# OLED_Display_Card.net
KiCad netlist of a schematic drawn in EAGLE
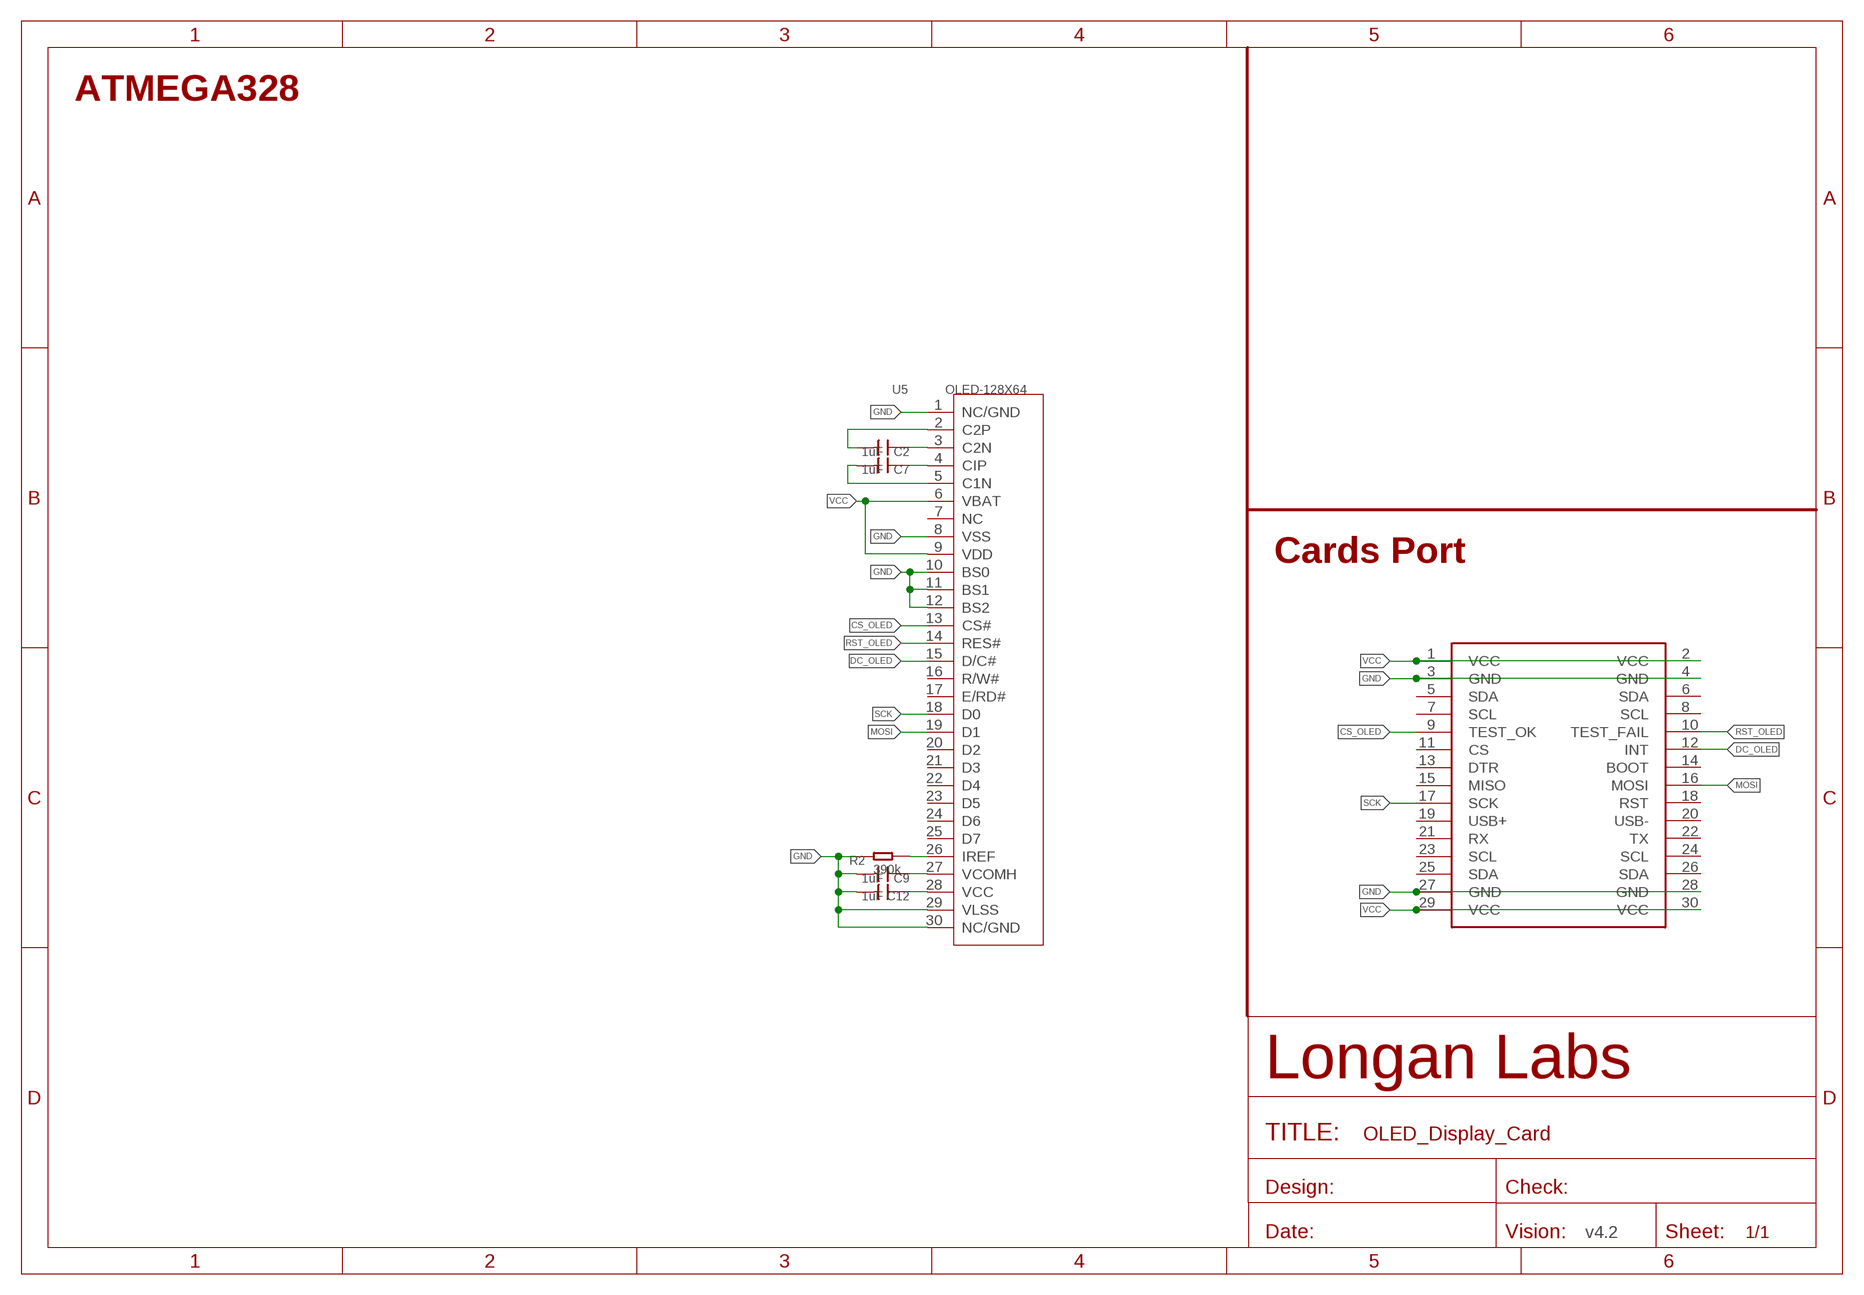
[diagram p0: schematic, sheet 1]

(export (version "E")
  (design (tool "Eeschema 10.0.6"))
  (components
    (comp (ref "C2")
      (value "1uF")
      (footprint "eagle-import:C0603@1")
      (libsource (lib "eagle-import") (part "C-0603"))
    )
    (comp (ref "C7")
      (value "1uF")
      (footprint "eagle-import:C0603@1")
      (libsource (lib "eagle-import") (part "C-0603"))
    )
    (comp (ref "C9")
      (value "1uF")
      (footprint "eagle-import:C0603@1")
      (libsource (lib "eagle-import") (part "C-0603"))
    )
    (comp (ref "C12")
      (value "1uF")
      (footprint "eagle-import:C0603@1")
      (libsource (lib "eagle-import") (part "C-0603"))
    )
    (comp (ref "MOUDLE1")
      (value "MOUDLE-2X15P-2.54")
      (footprint "eagle-import:MOUDLE-2X15P")
      (libsource (lib "eagle-import") (part "MOUDLE-2X15P-2.54"))
    )
    (comp (ref "R2")
      (value "390k")
      (footprint "eagle-import:R0603")
      (libsource (lib "eagle-import") (part "RES-0603"))
    )
    (comp (ref "U5")
      (value "OLED-128X64")
      (footprint "eagle-import:30P-0.7-34.5X12")
      (libsource (lib "eagle-import") (part "OLED-128X64"))
    )
  )
  (nets
    (net (code "1") (name "CS_OLED") (class "Default")
      (node (ref "MOUDLE1") (pin "9") (pinfunction "TEST_OK_9") (pintype "bidirectional"))
      (node (ref "U5") (pin "13") (pinfunction "CS#_13") (pintype "bidirectional"))
    )
    (net (code "2") (name "DC_OLED") (class "Default")
      (node (ref "MOUDLE1") (pin "12") (pinfunction "INT_12") (pintype "bidirectional"))
      (node (ref "U5") (pin "15") (pinfunction "D/C#_15") (pintype "bidirectional"))
    )
    (net (code "3") (name "GND") (class "Default")
      (node (ref "C12") (pin "2") (pinfunction "2_2") (pintype "passive"))
      (node (ref "C9") (pin "2") (pinfunction "2_2") (pintype "passive"))
      (node (ref "MOUDLE1") (pin "27") (pinfunction "GND_27") (pintype "bidirectional"))
      (node (ref "MOUDLE1") (pin "28") (pinfunction "GND_28") (pintype "bidirectional"))
      (node (ref "MOUDLE1") (pin "3") (pinfunction "GND_3") (pintype "bidirectional"))
      (node (ref "MOUDLE1") (pin "4") (pinfunction "GND_4") (pintype "bidirectional"))
      (node (ref "R2") (pin "1") (pinfunction "1_1") (pintype "passive"))
      (node (ref "U5") (pin "1") (pinfunction "NC/GND_1") (pintype "bidirectional"))
      (node (ref "U5") (pin "10") (pinfunction "BS0_10") (pintype "bidirectional"))
      (node (ref "U5") (pin "11") (pinfunction "BS1_11") (pintype "bidirectional"))
      (node (ref "U5") (pin "12") (pinfunction "BS2_12") (pintype "bidirectional"))
      (node (ref "U5") (pin "29") (pinfunction "VLSS_29") (pintype "bidirectional"))
      (node (ref "U5") (pin "30") (pinfunction "NC/GND_30") (pintype "bidirectional"))
      (node (ref "U5") (pin "8") (pinfunction "VSS_8") (pintype "bidirectional"))
    )
    (net (code "4") (name "MOSI") (class "Default")
      (node (ref "MOUDLE1") (pin "16") (pinfunction "MOSI_16") (pintype "bidirectional"))
      (node (ref "U5") (pin "19") (pinfunction "D1_19") (pintype "bidirectional"))
    )
    (net (code "5") (name "Net-(U5-C1N)") (class "Default")
      (node (ref "C7") (pin "2") (pinfunction "2_2") (pintype "passive"))
      (node (ref "U5") (pin "5") (pinfunction "C1N_5") (pintype "bidirectional"))
    )
    (net (code "6") (name "Net-(U5-C2N)") (class "Default")
      (node (ref "C2") (pin "1") (pinfunction "1_1") (pintype "passive"))
      (node (ref "U5") (pin "3") (pinfunction "C2N_3") (pintype "bidirectional"))
    )
    (net (code "7") (name "Net-(U5-C2P)") (class "Default")
      (node (ref "C2") (pin "2") (pinfunction "2_2") (pintype "passive"))
      (node (ref "U5") (pin "2") (pinfunction "C2P_2") (pintype "bidirectional"))
    )
    (net (code "8") (name "Net-(U5-CIP)") (class "Default")
      (node (ref "C7") (pin "1") (pinfunction "1_1") (pintype "passive"))
      (node (ref "U5") (pin "4") (pinfunction "CIP_4") (pintype "bidirectional"))
    )
    (net (code "9") (name "Net-(U5-IREF)") (class "Default")
      (node (ref "R2") (pin "2") (pinfunction "2_2") (pintype "passive"))
      (node (ref "U5") (pin "26") (pinfunction "IREF_26") (pintype "bidirectional"))
    )
    (net (code "10") (name "Net-(U5-VCC)") (class "Default")
      (node (ref "C12") (pin "1") (pinfunction "1_1") (pintype "passive"))
      (node (ref "U5") (pin "28") (pinfunction "VCC_28") (pintype "bidirectional"))
    )
    (net (code "11") (name "Net-(U5-VCOMH)") (class "Default")
      (node (ref "C9") (pin "1") (pinfunction "1_1") (pintype "passive"))
      (node (ref "U5") (pin "27") (pinfunction "VCOMH_27") (pintype "bidirectional"))
    )
    (net (code "12") (name "RST_OLED") (class "Default")
      (node (ref "MOUDLE1") (pin "10") (pinfunction "TEST_FAIL_10") (pintype "bidirectional"))
      (node (ref "U5") (pin "14") (pinfunction "RES#_14") (pintype "bidirectional"))
    )
    (net (code "13") (name "SCK") (class "Default")
      (node (ref "MOUDLE1") (pin "17") (pinfunction "SCK_17") (pintype "bidirectional"))
      (node (ref "U5") (pin "18") (pinfunction "D0_18") (pintype "bidirectional"))
    )
    (net (code "14") (name "VCC") (class "Default")
      (node (ref "MOUDLE1") (pin "1") (pinfunction "VCC_1") (pintype "bidirectional"))
      (node (ref "MOUDLE1") (pin "2") (pinfunction "VCC_2") (pintype "bidirectional"))
      (node (ref "MOUDLE1") (pin "29") (pinfunction "VCC_29") (pintype "bidirectional"))
      (node (ref "MOUDLE1") (pin "30") (pinfunction "VCC_30") (pintype "bidirectional"))
      (node (ref "U5") (pin "6") (pinfunction "VBAT_6") (pintype "bidirectional"))
      (node (ref "U5") (pin "9") (pinfunction "VDD_9") (pintype "bidirectional"))
    )
    (net (code "15") (name "unconnected-(MOUDLE1-BOOT-Pad14)") (class "Default")
      (node (ref "MOUDLE1") (pin "14") (pinfunction "BOOT_14") (pintype "bidirectional"))
    )
    (net (code "16") (name "unconnected-(MOUDLE1-CS-Pad11)") (class "Default")
      (node (ref "MOUDLE1") (pin "11") (pinfunction "CS_11") (pintype "bidirectional"))
    )
    (net (code "17") (name "unconnected-(MOUDLE1-DTR-Pad13)") (class "Default")
      (node (ref "MOUDLE1") (pin "13") (pinfunction "DTR_13") (pintype "bidirectional"))
    )
    (net (code "18") (name "unconnected-(MOUDLE1-MISO-Pad15)") (class "Default")
      (node (ref "MOUDLE1") (pin "15") (pinfunction "MISO_15") (pintype "bidirectional"))
    )
    (net (code "19") (name "unconnected-(MOUDLE1-RST-Pad18)") (class "Default")
      (node (ref "MOUDLE1") (pin "18") (pinfunction "RST_18") (pintype "bidirectional"))
    )
    (net (code "20") (name "unconnected-(MOUDLE1-RX-Pad21)") (class "Default")
      (node (ref "MOUDLE1") (pin "21") (pinfunction "RX_21") (pintype "bidirectional"))
    )
    (net (code "21") (name "unconnected-(MOUDLE1-SCL-Pad7)") (class "Default")
      (node (ref "MOUDLE1") (pin "7") (pinfunction "SCL_7") (pintype "bidirectional"))
    )
    (net (code "22") (name "unconnected-(MOUDLE1-SCL-Pad8)") (class "Default")
      (node (ref "MOUDLE1") (pin "8") (pinfunction "SCL_8") (pintype "bidirectional"))
    )
    (net (code "23") (name "unconnected-(MOUDLE1-SCL-Pad23)") (class "Default")
      (node (ref "MOUDLE1") (pin "23") (pinfunction "SCL_23") (pintype "bidirectional"))
    )
    (net (code "24") (name "unconnected-(MOUDLE1-SCL-Pad24)") (class "Default")
      (node (ref "MOUDLE1") (pin "24") (pinfunction "SCL_24") (pintype "bidirectional"))
    )
    (net (code "25") (name "unconnected-(MOUDLE1-SDA-Pad5)") (class "Default")
      (node (ref "MOUDLE1") (pin "5") (pinfunction "SDA_5") (pintype "bidirectional"))
    )
    (net (code "26") (name "unconnected-(MOUDLE1-SDA-Pad6)") (class "Default")
      (node (ref "MOUDLE1") (pin "6") (pinfunction "SDA_6") (pintype "bidirectional"))
    )
    (net (code "27") (name "unconnected-(MOUDLE1-SDA-Pad25)") (class "Default")
      (node (ref "MOUDLE1") (pin "25") (pinfunction "SDA_25") (pintype "bidirectional"))
    )
    (net (code "28") (name "unconnected-(MOUDLE1-SDA-Pad26)") (class "Default")
      (node (ref "MOUDLE1") (pin "26") (pinfunction "SDA_26") (pintype "bidirectional"))
    )
    (net (code "29") (name "unconnected-(MOUDLE1-TX-Pad22)") (class "Default")
      (node (ref "MOUDLE1") (pin "22") (pinfunction "TX_22") (pintype "bidirectional"))
    )
    (net (code "30") (name "unconnected-(MOUDLE1-USB+-Pad19)") (class "Default")
      (node (ref "MOUDLE1") (pin "19") (pinfunction "USB+_19") (pintype "bidirectional"))
    )
    (net (code "31") (name "unconnected-(MOUDLE1-USB--Pad20)") (class "Default")
      (node (ref "MOUDLE1") (pin "20") (pinfunction "USB-_20") (pintype "bidirectional"))
    )
    (net (code "32") (name "unconnected-(U5-D2-Pad20)") (class "Default")
      (node (ref "U5") (pin "20") (pinfunction "D2_20") (pintype "bidirectional"))
    )
    (net (code "33") (name "unconnected-(U5-D3-Pad21)") (class "Default")
      (node (ref "U5") (pin "21") (pinfunction "D3_21") (pintype "bidirectional"))
    )
    (net (code "34") (name "unconnected-(U5-D4-Pad22)") (class "Default")
      (node (ref "U5") (pin "22") (pinfunction "D4_22") (pintype "bidirectional"))
    )
    (net (code "35") (name "unconnected-(U5-D5-Pad23)") (class "Default")
      (node (ref "U5") (pin "23") (pinfunction "D5_23") (pintype "bidirectional"))
    )
    (net (code "36") (name "unconnected-(U5-D6-Pad24)") (class "Default")
      (node (ref "U5") (pin "24") (pinfunction "D6_24") (pintype "bidirectional"))
    )
    (net (code "37") (name "unconnected-(U5-D7-Pad25)") (class "Default")
      (node (ref "U5") (pin "25") (pinfunction "D7_25") (pintype "bidirectional"))
    )
    (net (code "38") (name "unconnected-(U5-E{slash}RD#-Pad17)") (class "Default")
      (node (ref "U5") (pin "17") (pinfunction "E/RD#_17") (pintype "bidirectional"))
    )
    (net (code "39") (name "unconnected-(U5-NC-Pad7)") (class "Default")
      (node (ref "U5") (pin "7") (pinfunction "NC_7") (pintype "bidirectional"))
    )
    (net (code "40") (name "unconnected-(U5-R{slash}W#-Pad16)") (class "Default")
      (node (ref "U5") (pin "16") (pinfunction "R/W#_16") (pintype "bidirectional"))
    )
  )
)
